# PLT-02-RevA.net
KiCad netlist of a schematic drawn in EAGLE
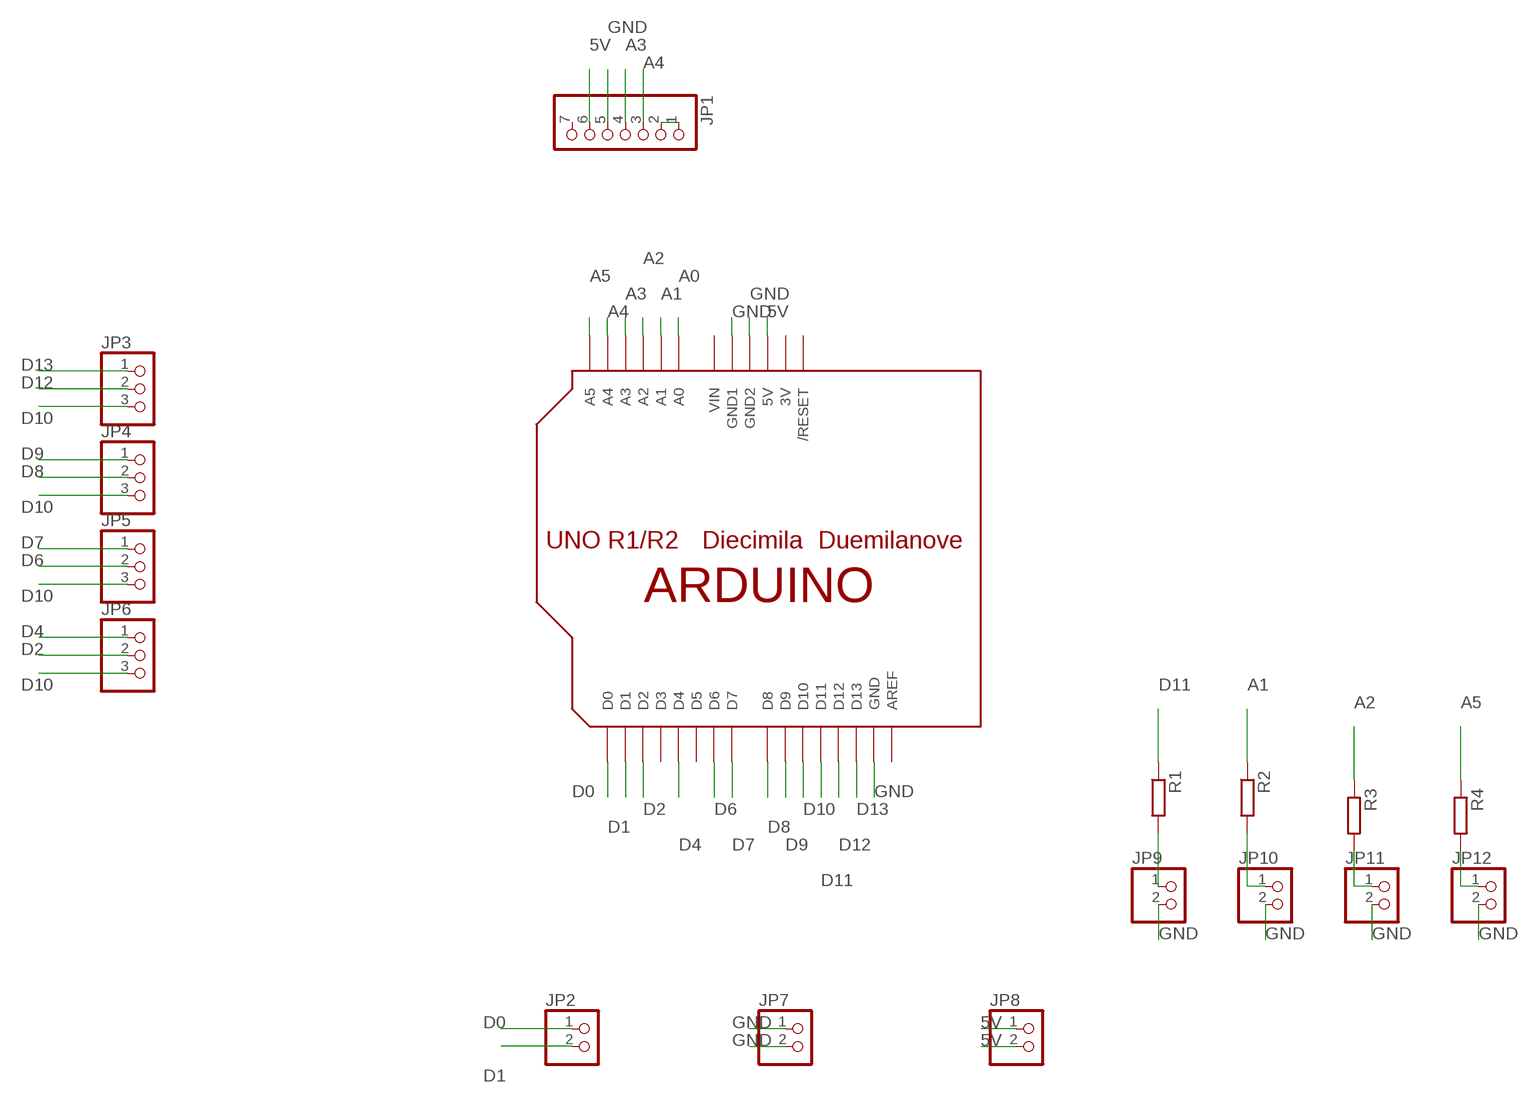
[diagram p0: schematic, sheet 1]

(export (version "E")
  (design (tool "Eeschema 10.0.6"))
  (components
    (comp (ref "JP1")
      (value "PINHD-1X7")
      (footprint "eagle-import:1X07")
      (libsource (lib "eagle-import") (part "PINHD-1X7"))
    )
    (comp (ref "JP2")
      (value "PINHD-1X2")
      (footprint "eagle-import:1X02")
      (libsource (lib "eagle-import") (part "PINHD-1X2"))
    )
    (comp (ref "JP3")
      (value "PINHD-1X3")
      (footprint "eagle-import:1X03")
      (libsource (lib "eagle-import") (part "PINHD-1X3"))
    )
    (comp (ref "JP4")
      (value "PINHD-1X3")
      (footprint "eagle-import:1X03")
      (libsource (lib "eagle-import") (part "PINHD-1X3"))
    )
    (comp (ref "JP5")
      (value "PINHD-1X3")
      (footprint "eagle-import:1X03")
      (libsource (lib "eagle-import") (part "PINHD-1X3"))
    )
    (comp (ref "JP6")
      (value "PINHD-1X3")
      (footprint "eagle-import:1X03")
      (libsource (lib "eagle-import") (part "PINHD-1X3"))
    )
    (comp (ref "JP7")
      (value "PINHD-1X2")
      (footprint "eagle-import:1X02")
      (libsource (lib "eagle-import") (part "PINHD-1X2"))
    )
    (comp (ref "JP8")
      (value "PINHD-1X2")
      (footprint "eagle-import:1X02")
      (libsource (lib "eagle-import") (part "PINHD-1X2"))
    )
    (comp (ref "JP9")
      (value "PINHD-1X2")
      (footprint "eagle-import:1X02")
      (libsource (lib "eagle-import") (part "PINHD-1X2"))
    )
    (comp (ref "JP10")
      (value "PINHD-1X2")
      (footprint "eagle-import:1X02")
      (libsource (lib "eagle-import") (part "PINHD-1X2"))
    )
    (comp (ref "JP11")
      (value "PINHD-1X2")
      (footprint "eagle-import:1X02")
      (libsource (lib "eagle-import") (part "PINHD-1X2"))
    )
    (comp (ref "JP12")
      (value "PINHD-1X2")
      (footprint "eagle-import:1X02")
      (libsource (lib "eagle-import") (part "PINHD-1X2"))
    )
    (comp (ref "R1")
      (value "R-EU_0207/10")
      (footprint "eagle-import:0207_10")
      (libsource (lib "eagle-import") (part "R-EU_0207/10"))
    )
    (comp (ref "R2")
      (value "R-EU_0207/10")
      (footprint "eagle-import:0207_10")
      (libsource (lib "eagle-import") (part "R-EU_0207/10"))
    )
    (comp (ref "R3")
      (value "R-EU_0207/10")
      (footprint "eagle-import:0207_10")
      (libsource (lib "eagle-import") (part "R-EU_0207/10"))
    )
    (comp (ref "R4")
      (value "R-EU_0207/10")
      (footprint "eagle-import:0207_10")
      (libsource (lib "eagle-import") (part "R-EU_0207/10"))
    )
    (comp (ref "U$1")
      (value "ARDUINOUNO")
      (footprint "eagle-import:ARDUINO")
      (libsource (lib "eagle-import") (part "ARDUINOUNO"))
    )
  )
  (nets
    (net (code "1") (name "/3V") (class "Default")
      (node (ref "U$1") (pin "3V") (pinfunction "3V_3V") (pintype "power_in"))
    )
    (net (code "2") (name "/5V") (class "Default")
      (node (ref "JP1") (pin "6") (pinfunction "6_6") (pintype "passive"))
      (node (ref "JP8") (pin "1") (pinfunction "1_1") (pintype "passive"))
      (node (ref "JP8") (pin "2") (pinfunction "2_2") (pintype "passive"))
      (node (ref "U$1") (pin "5V") (pinfunction "5V_5V") (pintype "power_in"))
    )
    (net (code "3") (name "/A0") (class "Default")
      (node (ref "U$1") (pin "A0") (pinfunction "A0_A0") (pintype "bidirectional"))
    )
    (net (code "4") (name "/A1") (class "Default")
      (node (ref "R2") (pin "1") (pinfunction "1_1") (pintype "passive"))
      (node (ref "U$1") (pin "A1") (pinfunction "A1_A1") (pintype "bidirectional"))
    )
    (net (code "5") (name "/A2") (class "Default")
      (node (ref "R3") (pin "1") (pinfunction "1_1") (pintype "passive"))
      (node (ref "U$1") (pin "A2") (pinfunction "A2_A2") (pintype "bidirectional"))
    )
    (net (code "6") (name "/A3") (class "Default")
      (node (ref "JP1") (pin "4") (pinfunction "4_4") (pintype "passive"))
      (node (ref "U$1") (pin "A3") (pinfunction "A3_A3") (pintype "bidirectional"))
    )
    (net (code "7") (name "/A4") (class "Default")
      (node (ref "JP1") (pin "3") (pinfunction "3_3") (pintype "passive"))
      (node (ref "U$1") (pin "A4") (pinfunction "A4_A4") (pintype "bidirectional"))
    )
    (net (code "8") (name "/A5") (class "Default")
      (node (ref "R4") (pin "1") (pinfunction "1_1") (pintype "passive"))
      (node (ref "U$1") (pin "A5") (pinfunction "A5_A5") (pintype "bidirectional"))
    )
    (net (code "9") (name "/D0") (class "Default")
      (node (ref "JP2") (pin "1") (pinfunction "1_1") (pintype "passive"))
      (node (ref "U$1") (pin "D0") (pinfunction "D0_D0") (pintype "bidirectional"))
    )
    (net (code "10") (name "/D1") (class "Default")
      (node (ref "JP2") (pin "2") (pinfunction "2_2") (pintype "passive"))
      (node (ref "U$1") (pin "D1") (pinfunction "D1_D1") (pintype "bidirectional"))
    )
    (net (code "11") (name "/D2") (class "Default")
      (node (ref "JP6") (pin "2") (pinfunction "2_2") (pintype "passive"))
      (node (ref "U$1") (pin "D2") (pinfunction "D2_D2") (pintype "bidirectional"))
    )
    (net (code "12") (name "/D4") (class "Default")
      (node (ref "JP6") (pin "1") (pinfunction "1_1") (pintype "passive"))
      (node (ref "U$1") (pin "D4") (pinfunction "D4_D4") (pintype "bidirectional"))
    )
    (net (code "13") (name "/D6") (class "Default")
      (node (ref "JP5") (pin "2") (pinfunction "2_2") (pintype "passive"))
      (node (ref "U$1") (pin "D6") (pinfunction "D6_D6") (pintype "bidirectional"))
    )
    (net (code "14") (name "/D7") (class "Default")
      (node (ref "JP5") (pin "1") (pinfunction "1_1") (pintype "passive"))
      (node (ref "U$1") (pin "D7") (pinfunction "D7_D7") (pintype "bidirectional"))
    )
    (net (code "15") (name "/D8") (class "Default")
      (node (ref "JP4") (pin "2") (pinfunction "2_2") (pintype "passive"))
      (node (ref "U$1") (pin "D8") (pinfunction "D8_D8") (pintype "bidirectional"))
    )
    (net (code "16") (name "/D9") (class "Default")
      (node (ref "JP4") (pin "1") (pinfunction "1_1") (pintype "passive"))
      (node (ref "U$1") (pin "D9") (pinfunction "D9_D9") (pintype "bidirectional"))
    )
    (net (code "17") (name "/D10") (class "Default")
      (node (ref "JP3") (pin "3") (pinfunction "3_3") (pintype "passive"))
      (node (ref "JP4") (pin "3") (pinfunction "3_3") (pintype "passive"))
      (node (ref "JP5") (pin "3") (pinfunction "3_3") (pintype "passive"))
      (node (ref "JP6") (pin "3") (pinfunction "3_3") (pintype "passive"))
      (node (ref "U$1") (pin "D10") (pinfunction "D10_D10") (pintype "bidirectional"))
    )
    (net (code "18") (name "/D11") (class "Default")
      (node (ref "R1") (pin "1") (pinfunction "1_1") (pintype "passive"))
      (node (ref "U$1") (pin "D11") (pinfunction "D11_D11") (pintype "bidirectional"))
    )
    (net (code "19") (name "/D12") (class "Default")
      (node (ref "JP3") (pin "2") (pinfunction "2_2") (pintype "passive"))
      (node (ref "U$1") (pin "D12") (pinfunction "D12_D12") (pintype "bidirectional"))
    )
    (net (code "20") (name "/D13") (class "Default")
      (node (ref "JP3") (pin "1") (pinfunction "1_1") (pintype "passive"))
      (node (ref "U$1") (pin "D13") (pinfunction "D13_D13") (pintype "bidirectional"))
    )
    (net (code "21") (name "/GND") (class "Default")
      (node (ref "JP1") (pin "5") (pinfunction "5_5") (pintype "passive"))
      (node (ref "JP10") (pin "2") (pinfunction "2_2") (pintype "passive"))
      (node (ref "JP11") (pin "2") (pinfunction "2_2") (pintype "passive"))
      (node (ref "JP12") (pin "2") (pinfunction "2_2") (pintype "passive"))
      (node (ref "JP7") (pin "1") (pinfunction "1_1") (pintype "passive"))
      (node (ref "JP7") (pin "2") (pinfunction "2_2") (pintype "passive"))
      (node (ref "JP9") (pin "2") (pinfunction "2_2") (pintype "passive"))
      (node (ref "U$1") (pin "GND") (pinfunction "GND_GND") (pintype "power_in"))
      (node (ref "U$1") (pin "GND1") (pinfunction "GND1_GND1") (pintype "power_in"))
      (node (ref "U$1") (pin "GND2") (pinfunction "GND2_GND2") (pintype "power_in"))
    )
    (net (code "22") (name "/VIN") (class "Default")
      (node (ref "U$1") (pin "VIN") (pinfunction "VIN_VIN") (pintype "power_in"))
    )
    (net (code "23") (name "Net-(JP1-Pad1)") (class "Default")
      (node (ref "JP1") (pin "1") (pinfunction "1_1") (pintype "passive"))
      (node (ref "JP1") (pin "2") (pinfunction "2_2") (pintype "passive"))
    )
    (net (code "24") (name "Net-(JP9-Pad1)") (class "Default")
      (node (ref "JP9") (pin "1") (pinfunction "1_1") (pintype "passive"))
      (node (ref "R1") (pin "2") (pinfunction "2_2") (pintype "passive"))
    )
    (net (code "25") (name "Net-(JP10-Pad1)") (class "Default")
      (node (ref "JP10") (pin "1") (pinfunction "1_1") (pintype "passive"))
      (node (ref "R2") (pin "2") (pinfunction "2_2") (pintype "passive"))
    )
    (net (code "26") (name "Net-(JP11-Pad1)") (class "Default")
      (node (ref "JP11") (pin "1") (pinfunction "1_1") (pintype "passive"))
      (node (ref "R3") (pin "2") (pinfunction "2_2") (pintype "passive"))
    )
    (net (code "27") (name "Net-(JP12-Pad1)") (class "Default")
      (node (ref "JP12") (pin "1") (pinfunction "1_1") (pintype "passive"))
      (node (ref "R4") (pin "2") (pinfunction "2_2") (pintype "passive"))
    )
    (net (code "28") (name "unconnected-(JP1-Pad7)") (class "Default")
      (node (ref "JP1") (pin "7") (pinfunction "7_7") (pintype "passive"))
    )
    (net (code "29") (name "unconnected-(U$1-PadAREF)") (class "Default")
      (node (ref "U$1") (pin "AREF") (pinfunction "AREF_AREF") (pintype "bidirectional"))
    )
    (net (code "30") (name "unconnected-(U$1-PadD3)") (class "Default")
      (node (ref "U$1") (pin "D3") (pinfunction "D3_D3") (pintype "bidirectional"))
    )
    (net (code "31") (name "unconnected-(U$1-PadD5)") (class "Default")
      (node (ref "U$1") (pin "D5") (pinfunction "D5_D5") (pintype "bidirectional"))
    )
    (net (code "32") (name "unconnected-(U$1-{slash}RESET-PadRESET)") (class "Default")
      (node (ref "U$1") (pin "RESET") (pinfunction "/RESET_RESET") (pintype "bidirectional"))
    )
  )
)
